# leddriver.net
KiCad netlist of a schematic drawn in Altium Designer
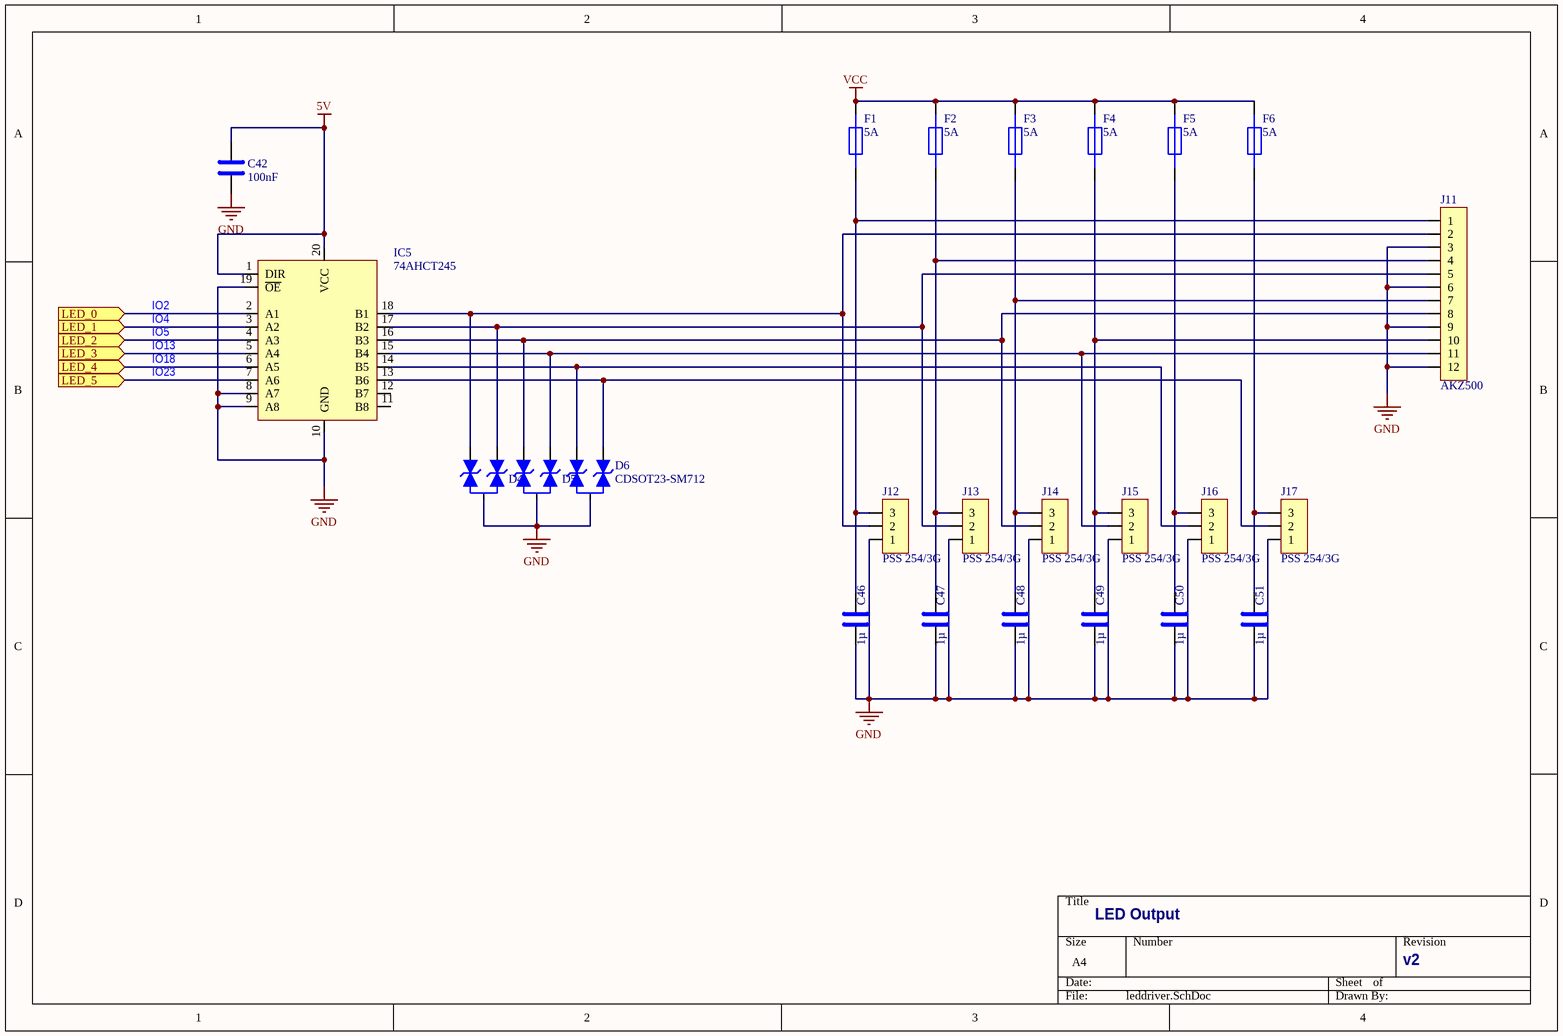
[diagram p0: leddriver.SchDoc]

(export (version "E")
  (design (tool "Eeschema 10.0.6"))
  (components
    (comp (ref "C42")
      (value "100nF")
      (footprint "0603")
      (description "100nF 50V MLCC 0603")
      (fields (field (name "VOLTAGE") "50V"))
      (libsource (lib "capacitors") (part "100nF 50V MLCC 0603"))
    )
    (comp (ref "C46")
      (value "1µ")
      (footprint "1206")
      (description "1µF 50V MLCC 1206")
      (fields (field (name "VOLTAGE") "50V"))
      (libsource (lib "capacitors") (part "1µF 50V MLCC 1206"))
    )
    (comp (ref "C47")
      (value "1µ")
      (footprint "1206")
      (description "1µF 50V MLCC 1206")
      (fields (field (name "VOLTAGE") "50V"))
      (libsource (lib "capacitors") (part "1µF 50V MLCC 1206"))
    )
    (comp (ref "C48")
      (value "1µ")
      (footprint "1206")
      (description "1µF 50V MLCC 1206")
      (fields (field (name "VOLTAGE") "50V"))
      (libsource (lib "capacitors") (part "1µF 50V MLCC 1206"))
    )
    (comp (ref "C49")
      (value "1µ")
      (footprint "1206")
      (description "1µF 50V MLCC 1206")
      (fields (field (name "VOLTAGE") "50V"))
      (libsource (lib "capacitors") (part "1µF 50V MLCC 1206"))
    )
    (comp (ref "C50")
      (value "1µ")
      (footprint "1206")
      (description "1µF 50V MLCC 1206")
      (fields (field (name "VOLTAGE") "50V"))
      (libsource (lib "capacitors") (part "1µF 50V MLCC 1206"))
    )
    (comp (ref "C51")
      (value "1µ")
      (footprint "1206")
      (description "1µF 50V MLCC 1206")
      (fields (field (name "VOLTAGE") "50V"))
      (libsource (lib "capacitors") (part "1µF 50V MLCC 1206"))
    )
    (comp (ref "D4")
      (value "CDSOT23-SM712")
      (footprint "SOT23")
      (description "Dual TVS diode")
      (libsource (lib "diodes") (part "CDSOT23-SM712"))
    )
    (comp (ref "D5")
      (value "CDSOT23-SM712")
      (footprint "SOT23")
      (description "Dual TVS diode")
      (libsource (lib "diodes") (part "CDSOT23-SM712"))
    )
    (comp (ref "D6")
      (value "CDSOT23-SM712")
      (footprint "SOT23")
      (description "Dual TVS diode")
      (libsource (lib "diodes") (part "CDSOT23-SM712"))
    )
    (comp (ref "F1")
      (value "5A")
      (footprint "1206")
      (description "Fuse, 1206, 5A, 63V")
      (libsource (lib "misc") (part "Fuse_1206_5A"))
    )
    (comp (ref "F2")
      (value "5A")
      (footprint "1206")
      (description "Fuse, 1206, 5A, 63V")
      (libsource (lib "misc") (part "Fuse_1206_5A"))
    )
    (comp (ref "F3")
      (value "5A")
      (footprint "1206")
      (description "Fuse, 1206, 5A, 63V")
      (libsource (lib "misc") (part "Fuse_1206_5A"))
    )
    (comp (ref "F4")
      (value "5A")
      (footprint "1206")
      (description "Fuse, 1206, 5A, 63V")
      (libsource (lib "misc") (part "Fuse_1206_5A"))
    )
    (comp (ref "F5")
      (value "5A")
      (footprint "1206")
      (description "Fuse, 1206, 5A, 63V")
      (libsource (lib "misc") (part "Fuse_1206_5A"))
    )
    (comp (ref "F6")
      (value "5A")
      (footprint "1206")
      (description "Fuse, 1206, 5A, 63V")
      (libsource (lib "misc") (part "Fuse_1206_5A"))
    )
    (comp (ref "IC5")
      (value "74AHCT245")
      (footprint "TSSOP20")
      (description "Octal Tristate Bus driver")
      (libsource (lib "misc") (part "SN74AHCT245"))
    )
    (comp (ref "J11")
      (value "AKZ500")
      (footprint "AKZ500/12")
      (libsource (lib "connectors_screw") (part "AKZ500/12"))
    )
    (comp (ref "J12")
      (value "PSS 254/3G")
      (footprint "PSS 3pol")
      (description "PSS 3pol wire-to-board-connector")
      (libsource (lib "connectors_pss") (part "PSS 254/3G"))
    )
    (comp (ref "J13")
      (value "PSS 254/3G")
      (footprint "PSS 3pol")
      (description "PSS 3pol wire-to-board-connector")
      (libsource (lib "connectors_pss") (part "PSS 254/3G"))
    )
    (comp (ref "J14")
      (value "PSS 254/3G")
      (footprint "PSS 3pol")
      (description "PSS 3pol wire-to-board-connector")
      (libsource (lib "connectors_pss") (part "PSS 254/3G"))
    )
    (comp (ref "J15")
      (value "PSS 254/3G")
      (footprint "PSS 3pol")
      (description "PSS 3pol wire-to-board-connector")
      (libsource (lib "connectors_pss") (part "PSS 254/3G"))
    )
    (comp (ref "J16")
      (value "PSS 254/3G")
      (footprint "PSS 3pol")
      (description "PSS 3pol wire-to-board-connector")
      (libsource (lib "connectors_pss") (part "PSS 254/3G"))
    )
    (comp (ref "J17")
      (value "PSS 254/3G")
      (footprint "PSS 3pol")
      (description "PSS 3pol wire-to-board-connector")
      (libsource (lib "connectors_pss") (part "PSS 254/3G"))
    )
  )
  (nets
    (net (code "1") (name "/LED_0") (class "Default")
      (node (ref "IC5") (pin "2") (pinfunction "A1_2") (pintype "passive"))
    )
    (net (code "2") (name "/LED_1") (class "Default")
      (node (ref "IC5") (pin "3") (pinfunction "A2_3") (pintype "passive"))
    )
    (net (code "3") (name "/LED_2") (class "Default")
      (node (ref "IC5") (pin "4") (pinfunction "A3_4") (pintype "passive"))
    )
    (net (code "4") (name "/LED_3") (class "Default")
      (node (ref "IC5") (pin "5") (pinfunction "A4_5") (pintype "passive"))
    )
    (net (code "5") (name "/LED_4") (class "Default")
      (node (ref "IC5") (pin "6") (pinfunction "A5_6") (pintype "passive"))
    )
    (net (code "6") (name "/LED_5") (class "Default")
      (node (ref "IC5") (pin "7") (pinfunction "A6_7") (pintype "passive"))
    )
    (net (code "7") (name "5V") (class "Default")
      (node (ref "C42") (pin "1") (pinfunction "1_1") (pintype "passive"))
      (node (ref "IC5") (pin "1") (pinfunction "DIR_1") (pintype "passive"))
      (node (ref "IC5") (pin "20") (pinfunction "VCC_20") (pintype "passive"))
    )
    (net (code "8") (name "GND") (class "Default")
      (node (ref "C42") (pin "2") (pinfunction "2_2") (pintype "passive"))
      (node (ref "C46") (pin "2") (pinfunction "2_2") (pintype "passive"))
      (node (ref "C47") (pin "2") (pinfunction "2_2") (pintype "passive"))
      (node (ref "C48") (pin "2") (pinfunction "2_2") (pintype "passive"))
      (node (ref "C49") (pin "2") (pinfunction "2_2") (pintype "passive"))
      (node (ref "C50") (pin "2") (pinfunction "2_2") (pintype "passive"))
      (node (ref "C51") (pin "2") (pinfunction "2_2") (pintype "passive"))
      (node (ref "D4") (pin "3") (pinfunction "3_3") (pintype "passive"))
      (node (ref "D5") (pin "3") (pinfunction "3_3") (pintype "passive"))
      (node (ref "D6") (pin "3") (pinfunction "3_3") (pintype "passive"))
      (node (ref "IC5") (pin "10") (pinfunction "GND_10") (pintype "passive"))
      (node (ref "IC5") (pin "19") (pinfunction "~{OE}_19") (pintype "passive"))
      (node (ref "IC5") (pin "8") (pinfunction "A7_8") (pintype "passive"))
      (node (ref "IC5") (pin "9") (pinfunction "A8_9") (pintype "passive"))
      (node (ref "J11") (pin "12") (pinfunction "12_12") (pintype "passive"))
      (node (ref "J11") (pin "3") (pinfunction "3_3") (pintype "passive"))
      (node (ref "J11") (pin "6") (pinfunction "6_6") (pintype "passive"))
      (node (ref "J11") (pin "9") (pinfunction "9_9") (pintype "passive"))
      (node (ref "J12") (pin "1") (pinfunction "1_1") (pintype "passive"))
      (node (ref "J13") (pin "1") (pinfunction "1_1") (pintype "passive"))
      (node (ref "J14") (pin "1") (pinfunction "1_1") (pintype "passive"))
      (node (ref "J15") (pin "1") (pinfunction "1_1") (pintype "passive"))
      (node (ref "J16") (pin "1") (pinfunction "1_1") (pintype "passive"))
      (node (ref "J17") (pin "1") (pinfunction "1_1") (pintype "passive"))
    )
    (net (code "9") (name "Net-(C46-Pad1)") (class "Default")
      (node (ref "C46") (pin "1") (pinfunction "1_1") (pintype "passive"))
      (node (ref "F1") (pin "1") (pinfunction "1_1") (pintype "passive"))
      (node (ref "J11") (pin "1") (pinfunction "1_1") (pintype "passive"))
      (node (ref "J12") (pin "3") (pinfunction "3_3") (pintype "passive"))
    )
    (net (code "10") (name "Net-(C47-Pad1)") (class "Default")
      (node (ref "C47") (pin "1") (pinfunction "1_1") (pintype "passive"))
      (node (ref "F2") (pin "1") (pinfunction "1_1") (pintype "passive"))
      (node (ref "J11") (pin "4") (pinfunction "4_4") (pintype "passive"))
      (node (ref "J13") (pin "3") (pinfunction "3_3") (pintype "passive"))
    )
    (net (code "11") (name "Net-(C48-Pad1)") (class "Default")
      (node (ref "C48") (pin "1") (pinfunction "1_1") (pintype "passive"))
      (node (ref "F3") (pin "1") (pinfunction "1_1") (pintype "passive"))
      (node (ref "J11") (pin "7") (pinfunction "7_7") (pintype "passive"))
      (node (ref "J14") (pin "3") (pinfunction "3_3") (pintype "passive"))
    )
    (net (code "12") (name "Net-(C49-Pad1)") (class "Default")
      (node (ref "C49") (pin "1") (pinfunction "1_1") (pintype "passive"))
      (node (ref "F4") (pin "1") (pinfunction "1_1") (pintype "passive"))
      (node (ref "J11") (pin "10") (pinfunction "10_10") (pintype "passive"))
      (node (ref "J15") (pin "3") (pinfunction "3_3") (pintype "passive"))
    )
    (net (code "13") (name "Net-(C50-Pad1)") (class "Default")
      (node (ref "C50") (pin "1") (pinfunction "1_1") (pintype "passive"))
      (node (ref "F5") (pin "1") (pinfunction "1_1") (pintype "passive"))
      (node (ref "J16") (pin "3") (pinfunction "3_3") (pintype "passive"))
    )
    (net (code "14") (name "Net-(C51-Pad1)") (class "Default")
      (node (ref "C51") (pin "1") (pinfunction "1_1") (pintype "passive"))
      (node (ref "F6") (pin "1") (pinfunction "1_1") (pintype "passive"))
      (node (ref "J17") (pin "3") (pinfunction "3_3") (pintype "passive"))
    )
    (net (code "15") (name "Net-(IC5-B1)") (class "Default")
      (node (ref "D4") (pin "1") (pinfunction "1_1") (pintype "passive"))
      (node (ref "IC5") (pin "18") (pinfunction "B1_18") (pintype "passive"))
      (node (ref "J11") (pin "2") (pinfunction "2_2") (pintype "passive"))
      (node (ref "J12") (pin "2") (pinfunction "2_2") (pintype "passive"))
    )
    (net (code "16") (name "Net-(IC5-B2)") (class "Default")
      (node (ref "D4") (pin "2") (pinfunction "2_2") (pintype "passive"))
      (node (ref "IC5") (pin "17") (pinfunction "B2_17") (pintype "passive"))
      (node (ref "J11") (pin "5") (pinfunction "5_5") (pintype "passive"))
      (node (ref "J13") (pin "2") (pinfunction "2_2") (pintype "passive"))
    )
    (net (code "17") (name "Net-(IC5-B3)") (class "Default")
      (node (ref "D5") (pin "1") (pinfunction "1_1") (pintype "passive"))
      (node (ref "IC5") (pin "16") (pinfunction "B3_16") (pintype "passive"))
      (node (ref "J11") (pin "8") (pinfunction "8_8") (pintype "passive"))
      (node (ref "J14") (pin "2") (pinfunction "2_2") (pintype "passive"))
    )
    (net (code "18") (name "Net-(IC5-B4)") (class "Default")
      (node (ref "D5") (pin "2") (pinfunction "2_2") (pintype "passive"))
      (node (ref "IC5") (pin "15") (pinfunction "B4_15") (pintype "passive"))
      (node (ref "J11") (pin "11") (pinfunction "11_11") (pintype "passive"))
      (node (ref "J15") (pin "2") (pinfunction "2_2") (pintype "passive"))
    )
    (net (code "19") (name "Net-(IC5-B5)") (class "Default")
      (node (ref "D6") (pin "1") (pinfunction "1_1") (pintype "passive"))
      (node (ref "IC5") (pin "14") (pinfunction "B5_14") (pintype "passive"))
      (node (ref "J16") (pin "2") (pinfunction "2_2") (pintype "passive"))
    )
    (net (code "20") (name "Net-(IC5-B6)") (class "Default")
      (node (ref "D6") (pin "2") (pinfunction "2_2") (pintype "passive"))
      (node (ref "IC5") (pin "13") (pinfunction "B6_13") (pintype "passive"))
      (node (ref "J17") (pin "2") (pinfunction "2_2") (pintype "passive"))
    )
    (net (code "21") (name "VCC") (class "Default")
      (node (ref "F1") (pin "2") (pinfunction "2_2") (pintype "passive"))
      (node (ref "F2") (pin "2") (pinfunction "2_2") (pintype "passive"))
      (node (ref "F3") (pin "2") (pinfunction "2_2") (pintype "passive"))
      (node (ref "F4") (pin "2") (pinfunction "2_2") (pintype "passive"))
      (node (ref "F5") (pin "2") (pinfunction "2_2") (pintype "passive"))
      (node (ref "F6") (pin "2") (pinfunction "2_2") (pintype "passive"))
    )
    (net (code "22") (name "unconnected-(IC5-B7-Pad12)") (class "Default")
      (node (ref "IC5") (pin "12") (pinfunction "B7_12") (pintype "passive"))
    )
    (net (code "23") (name "unconnected-(IC5-B8-Pad11)") (class "Default")
      (node (ref "IC5") (pin "11") (pinfunction "B8_11") (pintype "passive"))
    )
  )
)
